# SolenoidValveDriver_v01_Schematic.net
KiCad netlist of a schematic drawn in Altium Designer
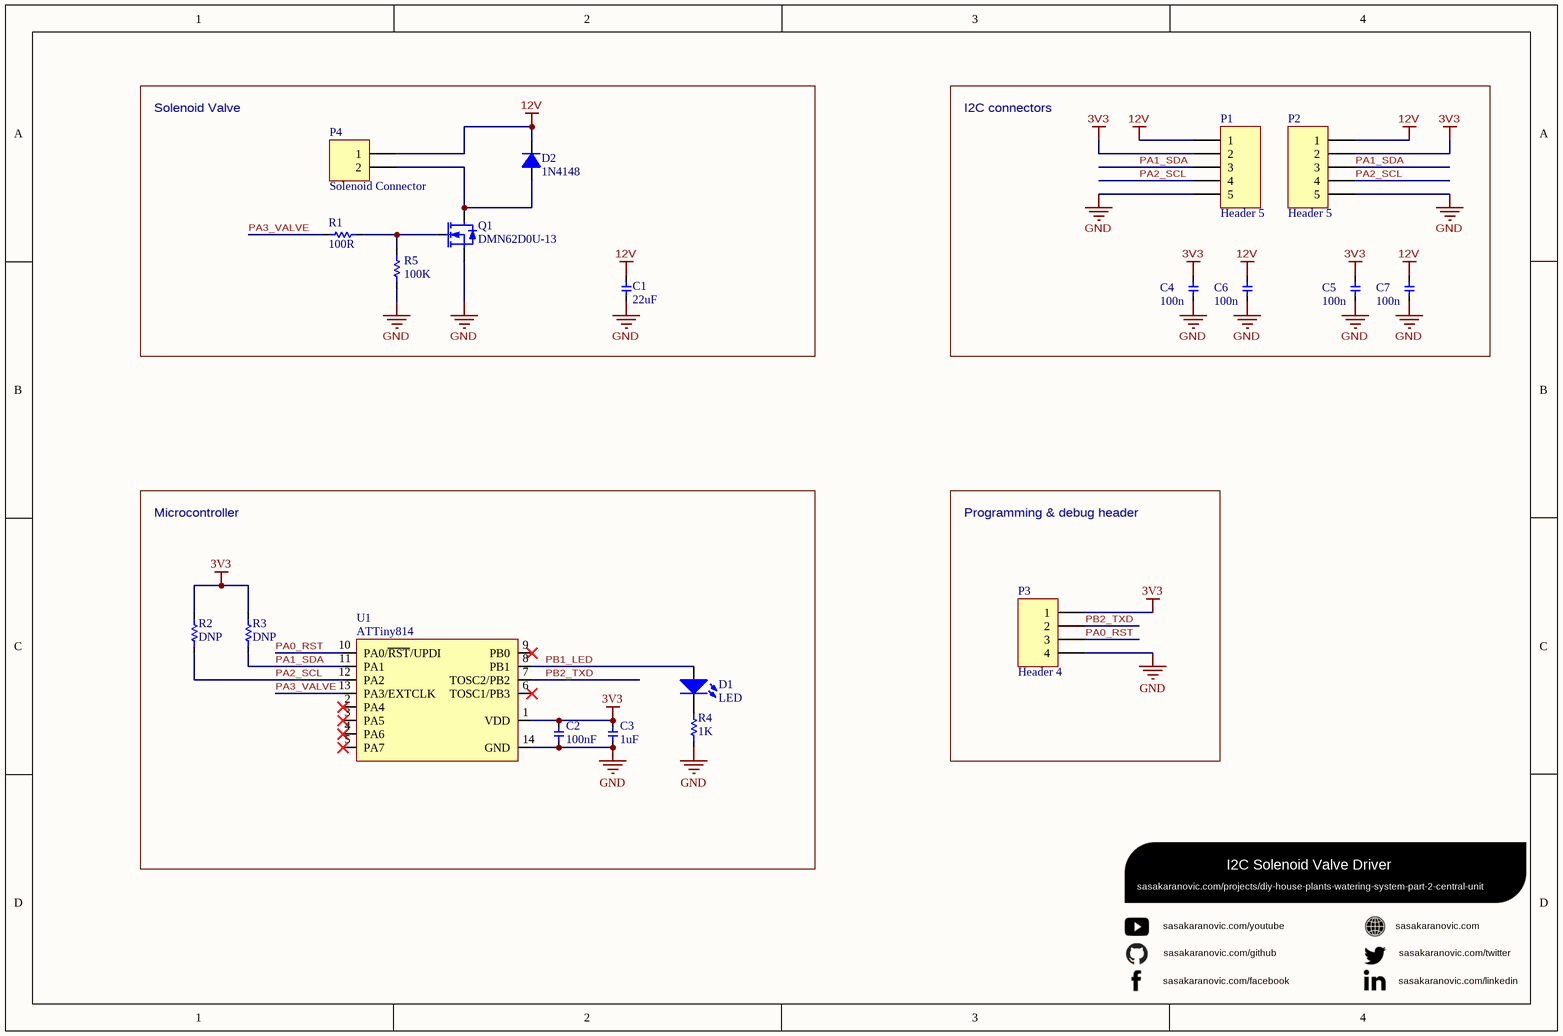
[diagram p0: SolenoidValveDriver_v01_Schematic.SchDoc]

(export (version "E")
  (design (tool "Eeschema 10.0.6"))
  (components
    (comp (ref "C1")
      (value "22uF")
      (footprint "Moji Footprintovi:0603 - CAP")
      (description "Capacitor")
      (fields
        (field (name "MANUFACTURER") "Nichicon")
        (field (name "MANUFACTURER PART NUMBER") "UVZ1J220MDD1TD")
      )
      (libsource (lib "Moji Schematici") (part "Cap"))
    )
    (comp (ref "C2")
      (value "100nF")
      (footprint "Moji Footprintovi:0603 - CAP")
      (description "Capacitor")
      (fields
        (field (name "MANUFACTURER") "Samsung Electro-Mechanics")
        (field (name "MANUFACTURER PART NUMBER") "CL10B104KB8NNNL")
      )
      (libsource (lib "Moji Schematici") (part "Cap"))
    )
    (comp (ref "C3")
      (value "1uF")
      (footprint "Moji Footprintovi:0603 - CAP")
      (description "Capacitor")
      (fields
        (field (name "MANUFACTURER") "Samsung Electro-Mechanics")
        (field (name "MANUFACTURER PART NUMBER") "CL31B105KBHNFNE")
      )
      (libsource (lib "Moji Schematici") (part "Cap"))
    )
    (comp (ref "C4")
      (value "100n")
      (footprint "Moji Footprintovi:0603 - CAP")
      (description "CAP CER 0.1UF 50V X7R 0603")
      (fields
        (field (name "MANUFACTURER") "Samsung Electro-Mechanics")
        (field (name "MANUFACTURER PART NUMBER") "CL10B104KB8NNNL")
      )
      (libsource (lib "Moji Schematici") (part "Cap"))
    )
    (comp (ref "C5")
      (value "100n")
      (footprint "Moji Footprintovi:0603 - CAP")
      (description "CAP CER 0.1UF 50V X7R 0603")
      (fields
        (field (name "MANUFACTURER") "Samsung Electro-Mechanics")
        (field (name "MANUFACTURER PART NUMBER") "CL10B104KB8NNNL")
      )
      (libsource (lib "Moji Schematici") (part "Cap"))
    )
    (comp (ref "C6")
      (value "100n")
      (footprint "Moji Footprintovi:0603 - CAP")
      (description "CAP CER 0.1UF 50V X7R 0603")
      (fields
        (field (name "MANUFACTURER") "Samsung Electro-Mechanics")
        (field (name "MANUFACTURER PART NUMBER") "CL10B104KB8NNNL")
      )
      (libsource (lib "Moji Schematici") (part "Cap"))
    )
    (comp (ref "C7")
      (value "100n")
      (footprint "Moji Footprintovi:0603 - CAP")
      (description "CAP CER 0.1UF 50V X7R 0603")
      (fields
        (field (name "MANUFACTURER") "Samsung Electro-Mechanics")
        (field (name "MANUFACTURER PART NUMBER") "CL10B104KB8NNNL")
      )
      (libsource (lib "Moji Schematici") (part "Cap"))
    )
    (comp (ref "D1")
      (value "LED")
      (footprint "Moji Footprintovi:0603 Diode")
      (description "Typical RED GaAs LED")
      (fields
        (field (name "DISTRIBUTOR PART NUMBER") "732-4978-1-ND")
        (field (name "MANUFACTURER") "Würth Elektronik")
      )
      (libsource (lib "Moji Schematici") (part "LED"))
    )
    (comp (ref "D2")
      (value "1N4148")
      (footprint "Moji Footprintovi:SOD123")
      (description "DIODE GEN PURP 100V 300MA SOD123")
      (fields
        (field (name "DISTRIBUTOR PART NUMBER") "1N4148W-FDICT-ND")
        (field (name "MANUFACTURER") "Diodes Incorporated")
      )
      (libsource (lib "Moji Schematici (1)") (part "Diode"))
    )
    (comp (ref "P1")
      (value "Header 5")
      (footprint "Moji Footprintovi:Header 5x1")
      (description "Header, 5-Pin")
      (fields
        (field (name "DISTRIBUTOR PART NUMBER") "952-2246-ND")
        (field (name "MANUFACTURER") "Harwin Inc.")
      )
      (libsource (lib "") (part "Header 5_1"))
    )
    (comp (ref "P2")
      (value "Header 5")
      (footprint "Moji Footprintovi:Header 5x1")
      (description "Header, 5-Pin")
      (fields
        (field (name "DISTRIBUTOR PART NUMBER") "952-2246-ND")
        (field (name "MANUFACTURER") "Harwin Inc.")
      )
      (libsource (lib "Moji Schematici") (part "Header 5"))
    )
    (comp (ref "P3")
      (value "Header 4")
      (footprint "Moji Footprintovi:Header 4x1")
      (description "Header, 4-Pin")
      (libsource (lib "Moji Schematici") (part "Header 4"))
    )
    (comp (ref "P4")
      (value "Solenoid Connector")
      (footprint "Moji Footprintovi:Header 2x1")
      (description "Header, 2-Pin")
      (fields
        (field (name "DISTRIBUTOR PART NUMBER") "952-2244-ND")
        (field (name "MANUFACTURER") "Harwin Inc.")
      )
      (libsource (lib "Moji Schematici") (part "Header 2"))
    )
    (comp (ref "Q1")
      (value "DMN62D0U-13")
      (footprint "Footprint_Misc:SOT90P240X100-3N")
      (description "MOSFET N-CH 60V 0.38A")
      (fields
        (field (name "MANUFACTURER") "Diodes Incorporated")
        (field (name "DISTRIBUTOR PART NUMBER") "DMN62D0U-13DICT-ND")
      )
      (libsource (lib "Schematic_Misc") (part "DMN62D0U-13"))
    )
    (comp (ref "R1")
      (value "100R")
      (footprint "Moji Footprintovi:0603")
      (description "RES SMD 0 OHM JUMPER 1/10W 0603")
      (fields (field (name "DISTRIBUTOR PART NUMBER") "311-0.0LECT-ND") (field (name "MANUFACTURER") "Yageo"))
      (libsource (lib "Moji Schematici") (part "Res"))
    )
    (comp (ref "R2")
      (value "DNP")
      (footprint "Moji Footprintovi:0603")
      (description "Resistor")
      (fields (field (name "Comment") "Res"))
      (libsource (lib "Moji Schematici") (part "Res"))
    )
    (comp (ref "R3")
      (value "DNP")
      (footprint "Moji Footprintovi:0603")
      (description "Resistor")
      (fields (field (name "Comment") "Res"))
      (libsource (lib "Moji Schematici") (part "Res"))
    )
    (comp (ref "R4")
      (value "1K")
      (footprint "Moji Footprintovi:0603")
      (description "Resistor")
      (fields
        (field (name "DISTRIBUTOR PART NUMBER") "311-1.0KGRCT-ND")
        (field (name "MANUFACTURER") "Yageo")
      )
      (libsource (lib "Moji Schematici") (part "Res"))
    )
    (comp (ref "R5")
      (value "100K")
      (footprint "Moji Footprintovi:0603")
      (description "RES SMD 1M OHM 5% 1/10W 0603")
      (fields
        (field (name "DISTRIBUTOR PART NUMBER") "311-1.0MGRCT-ND")
        (field (name "MANUFACTURER") "Yageo")
      )
      (libsource (lib "Moji Schematici") (part "Res"))
    )
    (comp (ref "U1")
      (value "ATTiny814")
      (footprint "Moji Footprintovi:SOIC127P600X175-14N")
      (description "IC MCU 8BIT 8KB FLASH 14SOIC")
      (fields
        (field (name "MANUFACTURER") "Microchip Technology")
        (field (name "MANUFACTURER PART NUMBER") "ATTINY814-SSNR")
      )
      (libsource (lib "Moji Schematici") (part "ATTiny814"))
    )
  )
  (nets
    (net (code "1") (name "/PA0_RST") (class "Default")
      (node (ref "P3") (pin "3") (pinfunction "3_3") (pintype "passive"))
      (node (ref "U1") (pin "10") (pinfunction "PA0/~{RST}/UPDI_10") (pintype "passive"))
    )
    (net (code "2") (name "/PA1_SDA") (class "Default")
      (node (ref "P1") (pin "3") (pinfunction "3_3") (pintype "passive"))
      (node (ref "P2") (pin "3") (pinfunction "3_3") (pintype "passive"))
      (node (ref "R3") (pin "1") (pinfunction "1_1") (pintype "passive"))
      (node (ref "U1") (pin "11") (pinfunction "PA1_11") (pintype "passive"))
    )
    (net (code "3") (name "/PA2_SCL") (class "Default")
      (node (ref "P1") (pin "4") (pinfunction "4_4") (pintype "passive"))
      (node (ref "P2") (pin "4") (pinfunction "4_4") (pintype "passive"))
      (node (ref "R2") (pin "1") (pinfunction "1_1") (pintype "passive"))
      (node (ref "U1") (pin "12") (pinfunction "PA2_12") (pintype "passive"))
    )
    (net (code "4") (name "/PA3_VALVE") (class "Default")
      (node (ref "R1") (pin "1") (pinfunction "1_1") (pintype "passive"))
      (node (ref "U1") (pin "13") (pinfunction "PA3/EXTCLK_13") (pintype "passive"))
    )
    (net (code "5") (name "/PB1_LED") (class "Default")
      (node (ref "D1") (pin "A") (pinfunction "A_A") (pintype "passive"))
      (node (ref "U1") (pin "8") (pinfunction "PB1_8") (pintype "passive"))
    )
    (net (code "6") (name "/PB2_TXD") (class "Default")
      (node (ref "P3") (pin "2") (pinfunction "2_2") (pintype "passive"))
      (node (ref "U1") (pin "7") (pinfunction "TOSC2/PB2_7") (pintype "passive"))
    )
    (net (code "7") (name "3V3") (class "Default")
      (node (ref "C2") (pin "2") (pinfunction "2_2") (pintype "passive"))
      (node (ref "C3") (pin "2") (pinfunction "2_2") (pintype "passive"))
      (node (ref "C4") (pin "2") (pinfunction "2_2") (pintype "passive"))
      (node (ref "C5") (pin "2") (pinfunction "2_2") (pintype "passive"))
      (node (ref "P1") (pin "2") (pinfunction "2_2") (pintype "passive"))
      (node (ref "P2") (pin "2") (pinfunction "2_2") (pintype "passive"))
      (node (ref "P3") (pin "1") (pinfunction "1_1") (pintype "passive"))
      (node (ref "R2") (pin "2") (pinfunction "2_2") (pintype "passive"))
      (node (ref "R3") (pin "2") (pinfunction "2_2") (pintype "passive"))
      (node (ref "U1") (pin "1") (pinfunction "VDD_1") (pintype "passive"))
    )
    (net (code "8") (name "12V") (class "Default")
      (node (ref "C1") (pin "2") (pinfunction "2_2") (pintype "passive"))
      (node (ref "C6") (pin "2") (pinfunction "2_2") (pintype "passive"))
      (node (ref "C7") (pin "2") (pinfunction "2_2") (pintype "passive"))
      (node (ref "D2") (pin "K") (pinfunction "K_K") (pintype "passive"))
      (node (ref "P1") (pin "1") (pinfunction "1_1") (pintype "passive"))
      (node (ref "P2") (pin "1") (pinfunction "1_1") (pintype "passive"))
      (node (ref "P4") (pin "1") (pinfunction "1_1") (pintype "passive"))
    )
    (net (code "9") (name "GND") (class "Default")
      (node (ref "C1") (pin "1") (pinfunction "1_1") (pintype "passive"))
      (node (ref "C2") (pin "1") (pinfunction "1_1") (pintype "passive"))
      (node (ref "C3") (pin "1") (pinfunction "1_1") (pintype "passive"))
      (node (ref "C4") (pin "1") (pinfunction "1_1") (pintype "passive"))
      (node (ref "C5") (pin "1") (pinfunction "1_1") (pintype "passive"))
      (node (ref "C6") (pin "1") (pinfunction "1_1") (pintype "passive"))
      (node (ref "C7") (pin "1") (pinfunction "1_1") (pintype "passive"))
      (node (ref "P1") (pin "5") (pinfunction "5_5") (pintype "passive"))
      (node (ref "P2") (pin "5") (pinfunction "5_5") (pintype "passive"))
      (node (ref "P3") (pin "4") (pinfunction "4_4") (pintype "passive"))
      (node (ref "Q1") (pin "2") (pinfunction "S_2") (pintype "passive"))
      (node (ref "R4") (pin "1") (pinfunction "1_1") (pintype "passive"))
      (node (ref "R5") (pin "1") (pinfunction "1_1") (pintype "passive"))
      (node (ref "U1") (pin "14") (pinfunction "GND_14") (pintype "passive"))
    )
    (net (code "10") (name "Net-(D1-PadK)") (class "Default")
      (node (ref "D1") (pin "K") (pinfunction "K_K") (pintype "passive"))
      (node (ref "R4") (pin "2") (pinfunction "2_2") (pintype "passive"))
    )
    (net (code "11") (name "Net-(Q1-D)") (class "Default")
      (node (ref "D2") (pin "A") (pinfunction "A_A") (pintype "passive"))
      (node (ref "P4") (pin "2") (pinfunction "2_2") (pintype "passive"))
      (node (ref "Q1") (pin "3") (pinfunction "D_3") (pintype "passive"))
    )
    (net (code "12") (name "Net-(Q1-G)") (class "Default")
      (node (ref "Q1") (pin "1") (pinfunction "G_1") (pintype "passive"))
      (node (ref "R1") (pin "2") (pinfunction "2_2") (pintype "passive"))
      (node (ref "R5") (pin "2") (pinfunction "2_2") (pintype "passive"))
    )
    (net (code "13") (name "unconnected-(U1-PA4-Pad2)") (class "Default")
      (node (ref "U1") (pin "2") (pinfunction "PA4_2") (pintype "passive+no_connect"))
    )
    (net (code "14") (name "unconnected-(U1-PA5-Pad3)") (class "Default")
      (node (ref "U1") (pin "3") (pinfunction "PA5_3") (pintype "passive+no_connect"))
    )
    (net (code "15") (name "unconnected-(U1-PA6-Pad4)") (class "Default")
      (node (ref "U1") (pin "4") (pinfunction "PA6_4") (pintype "passive+no_connect"))
    )
    (net (code "16") (name "unconnected-(U1-PA7-Pad5)") (class "Default")
      (node (ref "U1") (pin "5") (pinfunction "PA7_5") (pintype "passive+no_connect"))
    )
    (net (code "17") (name "unconnected-(U1-PB0-Pad9)") (class "Default")
      (node (ref "U1") (pin "9") (pinfunction "PB0_9") (pintype "passive+no_connect"))
    )
    (net (code "18") (name "unconnected-(U1-TOSC1{slash}PB3-Pad6)") (class "Default")
      (node (ref "U1") (pin "6") (pinfunction "TOSC1/PB3_6") (pintype "passive+no_connect"))
    )
  )
)
